# LokomotivATMega328RevA.net
KiCad netlist of a schematic drawn in EAGLE
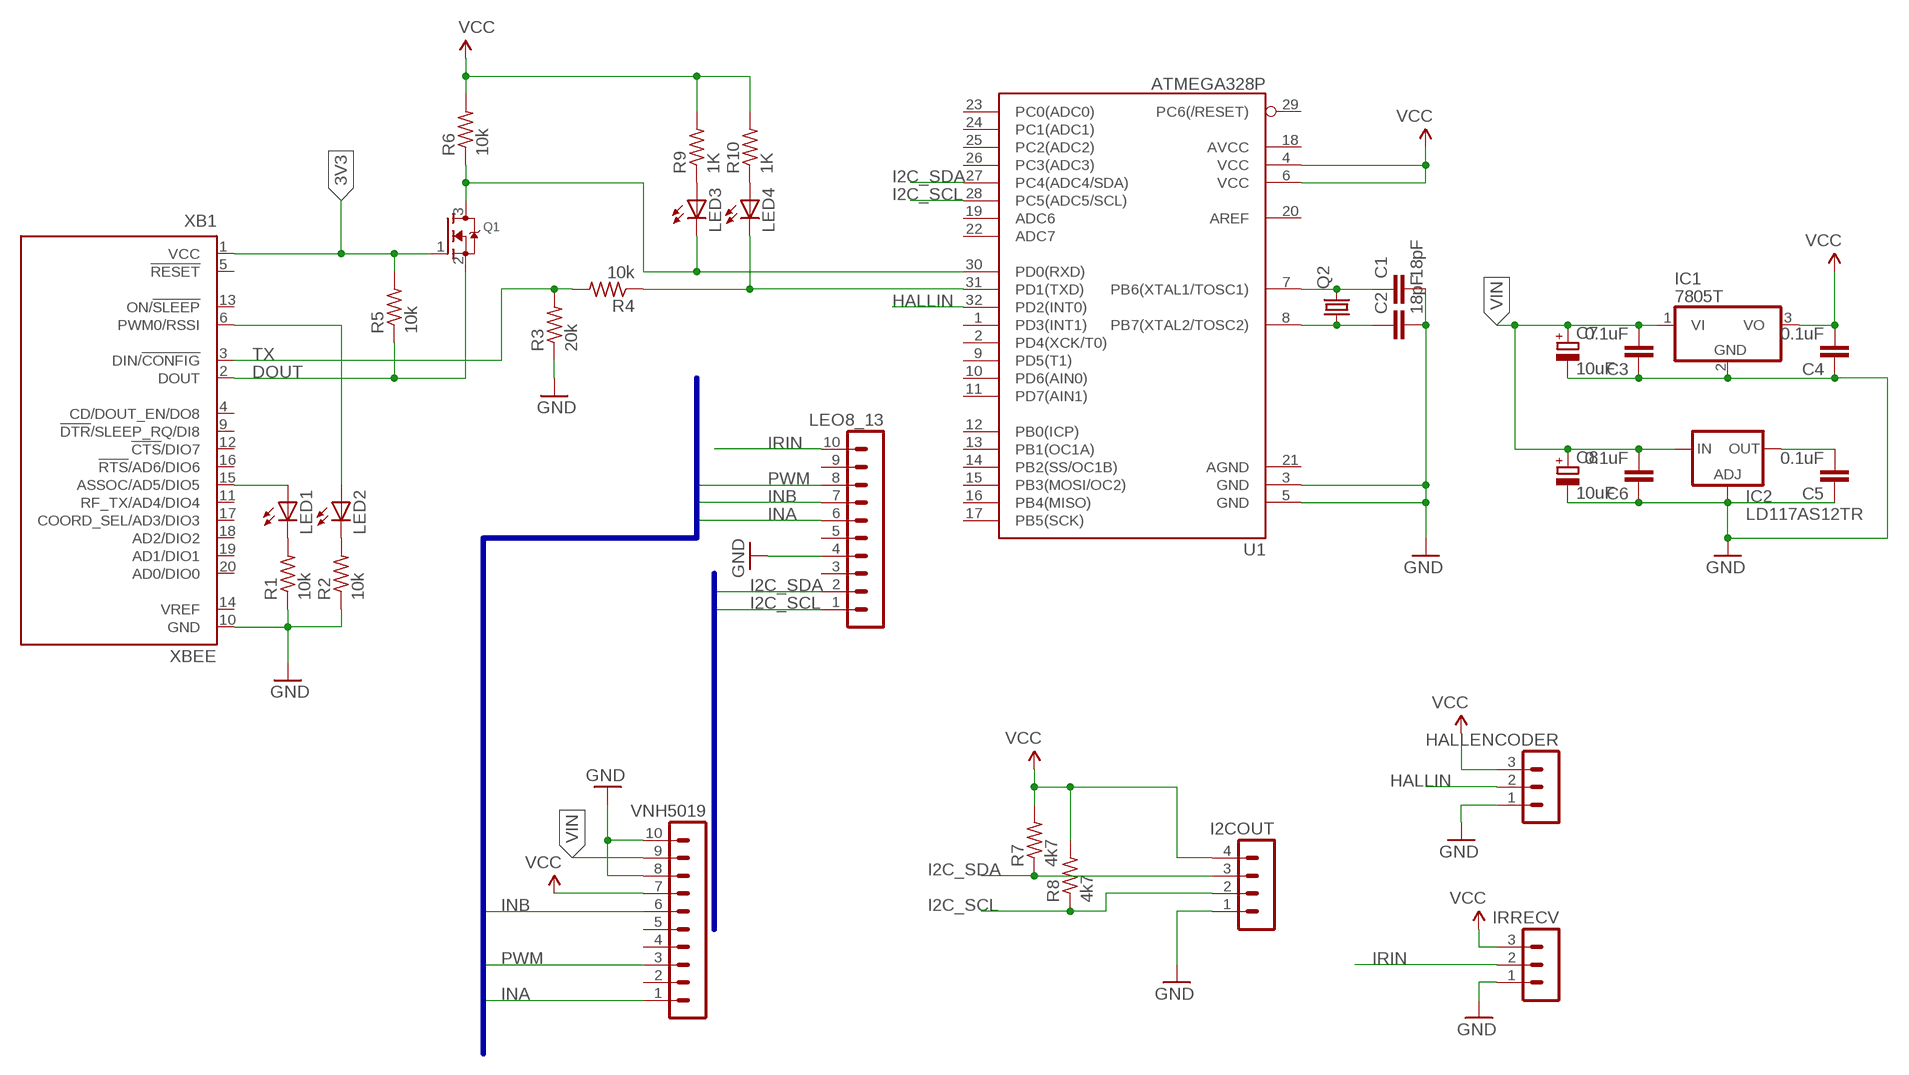
[diagram p0: schematic, sheet 1]

(export (version "E")
  (design (tool "Eeschema 10.0.6"))
  (components
    (comp (ref "C1")
      (value "18pF")
      (footprint "eagle-import:0603-CAP")
      (libsource (lib "eagle-import") (part "CAP0603-CAP"))
    )
    (comp (ref "C2")
      (value "18pF")
      (footprint "eagle-import:0603-CAP")
      (libsource (lib "eagle-import") (part "CAP0603-CAP"))
    )
    (comp (ref "C3")
      (value "0.1uF")
      (footprint "eagle-import:0603-CAP")
      (libsource (lib "eagle-import") (part "CAP0603-CAP"))
    )
    (comp (ref "C4")
      (value "0.1uF")
      (footprint "eagle-import:0603-CAP")
      (libsource (lib "eagle-import") (part "CAP0603-CAP"))
    )
    (comp (ref "C5")
      (value "0.1uF")
      (footprint "eagle-import:0603-CAP")
      (libsource (lib "eagle-import") (part "CAP0603-CAP"))
    )
    (comp (ref "C6")
      (value "0.1uF")
      (footprint "eagle-import:0603-CAP")
      (libsource (lib "eagle-import") (part "CAP0603-CAP"))
    )
    (comp (ref "C7")
      (value "10uF")
      (footprint "eagle-import:E3,5-10")
      (libsource (lib "eagle-import") (part "CPOL-EUE3.5-10"))
    )
    (comp (ref "C8")
      (value "10uF")
      (footprint "eagle-import:E3,5-10")
      (libsource (lib "eagle-import") (part "CPOL-EUE3.5-10"))
    )
    (comp (ref "HALLENCODER")
      (value "MA03-1")
      (footprint "eagle-import:MA03-1")
      (libsource (lib "eagle-import") (part "MA03-1"))
    )
    (comp (ref "I2COUT")
      (value "MA04-1")
      (footprint "eagle-import:MA04-1")
      (libsource (lib "eagle-import") (part "MA04-1"))
    )
    (comp (ref "IC1")
      (value "7805T")
      (footprint "eagle-import:TO220H")
      (libsource (lib "eagle-import") (part "78T05"))
    )
    (comp (ref "IC2")
      (value "LD117AS12TR")
      (footprint "eagle-import:SOT223")
      (libsource (lib "eagle-import") (part "LD117A?S12TR"))
    )
    (comp (ref "IRRECV")
      (value "MA03-1")
      (footprint "eagle-import:MA03-1")
      (libsource (lib "eagle-import") (part "MA03-1"))
    )
    (comp (ref "LED1")
      (value "LED-FKIT-1206")
      (footprint "eagle-import:FKIT-LED-1206")
      (libsource (lib "eagle-import") (part "LED-FKIT-1206"))
    )
    (comp (ref "LED2")
      (value "LED-FKIT-1206")
      (footprint "eagle-import:FKIT-LED-1206")
      (libsource (lib "eagle-import") (part "LED-FKIT-1206"))
    )
    (comp (ref "LED3")
      (value "LED-FKIT-1206")
      (footprint "eagle-import:FKIT-LED-1206")
      (libsource (lib "eagle-import") (part "LED-FKIT-1206"))
    )
    (comp (ref "LED4")
      (value "LED-FKIT-1206")
      (footprint "eagle-import:FKIT-LED-1206")
      (libsource (lib "eagle-import") (part "LED-FKIT-1206"))
    )
    (comp (ref "LEO8_13")
      (value "MA10-1")
      (footprint "eagle-import:MA10-1")
      (libsource (lib "eagle-import") (part "MA10-1"))
    )
    (comp (ref "Q1")
      (value "MOSFET-NREFLOW")
      (footprint "eagle-import:SOT23")
      (libsource (lib "eagle-import") (part "MOSFET-NREFLOW"))
    )
    (comp (ref "Q2")
      (value "CRYSTALSM49")
      (footprint "eagle-import:SM49")
      (libsource (lib "eagle-import") (part "CRYSTALSM49"))
    )
    (comp (ref "R1")
      (value "10k")
      (footprint "eagle-import:R0805")
      (libsource (lib "eagle-import") (part "R-US_R0805"))
    )
    (comp (ref "R2")
      (value "10k")
      (footprint "eagle-import:R0805")
      (libsource (lib "eagle-import") (part "R-US_R0805"))
    )
    (comp (ref "R3")
      (value "20k")
      (footprint "eagle-import:R0805")
      (libsource (lib "eagle-import") (part "R-US_R0805"))
    )
    (comp (ref "R4")
      (value "10k")
      (footprint "eagle-import:R0805")
      (libsource (lib "eagle-import") (part "R-US_R0805"))
    )
    (comp (ref "R5")
      (value "10k")
      (footprint "eagle-import:R0805")
      (libsource (lib "eagle-import") (part "R-US_R0805"))
    )
    (comp (ref "R6")
      (value "10k")
      (footprint "eagle-import:R0805")
      (libsource (lib "eagle-import") (part "R-US_R0805"))
    )
    (comp (ref "R7")
      (value "4k7")
      (footprint "eagle-import:R0805")
      (libsource (lib "eagle-import") (part "R-US_R0805"))
    )
    (comp (ref "R8")
      (value "4k7")
      (footprint "eagle-import:R0805")
      (libsource (lib "eagle-import") (part "R-US_R0805"))
    )
    (comp (ref "R9")
      (value "1K")
      (footprint "eagle-import:R0805")
      (libsource (lib "eagle-import") (part "R-US_R0805"))
    )
    (comp (ref "R10")
      (value "1K")
      (footprint "eagle-import:R0805")
      (libsource (lib "eagle-import") (part "R-US_R0805"))
    )
    (comp (ref "U1")
      (value "ATMEGA328P")
      (footprint "eagle-import:TQFP32-08")
      (libsource (lib "eagle-import") (part "ATMEGA328_SMT"))
    )
    (comp (ref "VNH5019")
      (value "MA10-1")
      (footprint "eagle-import:MA10-1")
      (libsource (lib "eagle-import") (part "MA10-1"))
    )
    (comp (ref "XB1")
      (value "XBEE")
      (footprint "eagle-import:XBEE")
      (fields (field (name "MPN") "XBP24-Z7UIT-004"))
      (libsource (lib "eagle-import") (part "XBEE"))
    )
  )
  (nets
    (net (code "1") (name "/DOUT") (class "Default")
      (node (ref "Q1") (pin "2") (pinfunction "S_2") (pintype "bidirectional"))
      (node (ref "R5") (pin "1") (pinfunction "1_1") (pintype "passive"))
      (node (ref "XB1") (pin "2") (pinfunction "DOUT_2") (pintype "output"))
    )
    (net (code "2") (name "/HALLIN") (class "Default")
      (node (ref "HALLENCODER") (pin "2") (pinfunction "2_2") (pintype "passive"))
      (node (ref "U1") (pin "32") (pinfunction "PD2(INT0)_32") (pintype "bidirectional"))
    )
    (net (code "3") (name "/I2C_SCL") (class "Default")
      (node (ref "I2COUT") (pin "2") (pinfunction "2_2") (pintype "passive"))
      (node (ref "LEO8_13") (pin "1") (pinfunction "1_1") (pintype "passive"))
      (node (ref "R8") (pin "1") (pinfunction "1_1") (pintype "passive"))
      (node (ref "U1") (pin "28") (pinfunction "PC5(ADC5/SCL)_28") (pintype "bidirectional"))
    )
    (net (code "4") (name "/I2C_SDA") (class "Default")
      (node (ref "I2COUT") (pin "3") (pinfunction "3_3") (pintype "passive"))
      (node (ref "LEO8_13") (pin "2") (pinfunction "2_2") (pintype "passive"))
      (node (ref "R7") (pin "1") (pinfunction "1_1") (pintype "passive"))
      (node (ref "U1") (pin "27") (pinfunction "PC4(ADC4/SDA)_27") (pintype "bidirectional"))
    )
    (net (code "5") (name "/INA") (class "Default")
      (node (ref "LEO8_13") (pin "6") (pinfunction "6_6") (pintype "passive"))
      (node (ref "VNH5019") (pin "1") (pinfunction "1_1") (pintype "passive"))
    )
    (net (code "6") (name "/INB") (class "Default")
      (node (ref "LEO8_13") (pin "7") (pinfunction "7_7") (pintype "passive"))
      (node (ref "VNH5019") (pin "6") (pinfunction "6_6") (pintype "passive"))
    )
    (net (code "7") (name "/IRIN") (class "Default")
      (node (ref "IRRECV") (pin "2") (pinfunction "2_2") (pintype "passive"))
      (node (ref "LEO8_13") (pin "10") (pinfunction "10_10") (pintype "passive"))
    )
    (net (code "8") (name "/PWM") (class "Default")
      (node (ref "LEO8_13") (pin "8") (pinfunction "8_8") (pintype "passive"))
      (node (ref "VNH5019") (pin "3") (pinfunction "3_3") (pintype "passive"))
    )
    (net (code "9") (name "/TX") (class "Default")
      (node (ref "R3") (pin "2") (pinfunction "2_2") (pintype "passive"))
      (node (ref "R4") (pin "2") (pinfunction "2_2") (pintype "passive"))
      (node (ref "XB1") (pin "3") (pinfunction "DIN/~{CONFIG}_3") (pintype "input"))
    )
    (net (code "10") (name "3V3") (class "Default")
      (node (ref "Q1") (pin "1") (pinfunction "G_1") (pintype "bidirectional"))
      (node (ref "R5") (pin "2") (pinfunction "2_2") (pintype "passive"))
      (node (ref "XB1") (pin "1") (pinfunction "VCC_1") (pintype "power_in"))
    )
    (net (code "11") (name "GND") (class "Default")
      (node (ref "C1") (pin "2") (pinfunction "2_2") (pintype "passive"))
      (node (ref "C2") (pin "2") (pinfunction "2_2") (pintype "passive"))
      (node (ref "C3") (pin "1") (pinfunction "1_1") (pintype "passive"))
      (node (ref "C4") (pin "1") (pinfunction "1_1") (pintype "passive"))
      (node (ref "C5") (pin "1") (pinfunction "1_1") (pintype "passive"))
      (node (ref "C6") (pin "1") (pinfunction "1_1") (pintype "passive"))
      (node (ref "C7") (pin "-") (pinfunction "-_-") (pintype "passive"))
      (node (ref "C8") (pin "-") (pinfunction "-_-") (pintype "passive"))
      (node (ref "HALLENCODER") (pin "1") (pinfunction "1_1") (pintype "passive"))
      (node (ref "I2COUT") (pin "1") (pinfunction "1_1") (pintype "passive"))
      (node (ref "IC1") (pin "2") (pinfunction "GND_2") (pintype "passive"))
      (node (ref "IC2") (pin "1") (pinfunction "ADJ_1") (pintype "input"))
      (node (ref "IRRECV") (pin "1") (pinfunction "1_1") (pintype "passive"))
      (node (ref "LEO8_13") (pin "4") (pinfunction "4_4") (pintype "passive"))
      (node (ref "R1") (pin "1") (pinfunction "1_1") (pintype "passive"))
      (node (ref "R2") (pin "1") (pinfunction "1_1") (pintype "passive"))
      (node (ref "R3") (pin "1") (pinfunction "1_1") (pintype "passive"))
      (node (ref "U1") (pin "3") (pinfunction "GND_3") (pintype "bidirectional"))
      (node (ref "U1") (pin "5") (pinfunction "GND_5") (pintype "bidirectional"))
      (node (ref "VNH5019") (pin "10") (pinfunction "10_10") (pintype "passive"))
      (node (ref "VNH5019") (pin "8") (pinfunction "8_8") (pintype "passive"))
      (node (ref "XB1") (pin "10") (pinfunction "GND_10") (pintype "power_in"))
    )
    (net (code "12") (name "Net-(IC2-OUT)") (class "Default")
      (node (ref "C5") (pin "2") (pinfunction "2_2") (pintype "passive"))
      (node (ref "IC2") (pin "4") (pinfunction "OUT_4") (pintype "passive"))
    )
    (net (code "13") (name "Net-(LED1-PadC)") (class "Default")
      (node (ref "LED1") (pin "C") (pinfunction "C_C") (pintype "passive"))
      (node (ref "R1") (pin "2") (pinfunction "2_2") (pintype "passive"))
    )
    (net (code "14") (name "Net-(LED2-PadC)") (class "Default")
      (node (ref "LED2") (pin "C") (pinfunction "C_C") (pintype "passive"))
      (node (ref "R2") (pin "2") (pinfunction "2_2") (pintype "passive"))
    )
    (net (code "15") (name "Net-(LED3-PadA)") (class "Default")
      (node (ref "LED3") (pin "A") (pinfunction "A_A") (pintype "passive"))
      (node (ref "R9") (pin "1") (pinfunction "1_1") (pintype "passive"))
    )
    (net (code "16") (name "Net-(LED4-PadA)") (class "Default")
      (node (ref "LED4") (pin "A") (pinfunction "A_A") (pintype "passive"))
      (node (ref "R10") (pin "1") (pinfunction "1_1") (pintype "passive"))
    )
    (net (code "17") (name "Net-(Q1-D)") (class "Default")
      (node (ref "LED3") (pin "C") (pinfunction "C_C") (pintype "passive"))
      (node (ref "Q1") (pin "3") (pinfunction "D_3") (pintype "bidirectional"))
      (node (ref "R6") (pin "1") (pinfunction "1_1") (pintype "passive"))
      (node (ref "U1") (pin "30") (pinfunction "PD0(RXD)_30") (pintype "bidirectional"))
    )
    (net (code "18") (name "Net-(U1-PB6(XTAL1{slash}TOSC1))") (class "Default")
      (node (ref "C1") (pin "1") (pinfunction "1_1") (pintype "passive"))
      (node (ref "Q2") (pin "2") (pinfunction "2_2") (pintype "passive"))
      (node (ref "U1") (pin "7") (pinfunction "PB6(XTAL1/TOSC1)_7") (pintype "bidirectional"))
    )
    (net (code "19") (name "Net-(U1-PB7(XTAL2{slash}TOSC2))") (class "Default")
      (node (ref "C2") (pin "1") (pinfunction "1_1") (pintype "passive"))
      (node (ref "Q2") (pin "1") (pinfunction "1_1") (pintype "passive"))
      (node (ref "U1") (pin "8") (pinfunction "PB7(XTAL2/TOSC2)_8") (pintype "bidirectional"))
    )
    (net (code "20") (name "Net-(U1-PD1(TXD))") (class "Default")
      (node (ref "LED4") (pin "C") (pinfunction "C_C") (pintype "passive"))
      (node (ref "R4") (pin "1") (pinfunction "1_1") (pintype "passive"))
      (node (ref "U1") (pin "31") (pinfunction "PD1(TXD)_31") (pintype "bidirectional"))
    )
    (net (code "21") (name "Net-(XB1-ASSOC{slash}AD5{slash}DIO5)") (class "Default")
      (node (ref "LED1") (pin "A") (pinfunction "A_A") (pintype "passive"))
      (node (ref "XB1") (pin "15") (pinfunction "ASSOC/AD5/DIO5_15") (pintype "bidirectional"))
    )
    (net (code "22") (name "Net-(XB1-PWM0{slash}RSSI)") (class "Default")
      (node (ref "LED2") (pin "A") (pinfunction "A_A") (pintype "passive"))
      (node (ref "XB1") (pin "6") (pinfunction "PWM0/RSSI_6") (pintype "output"))
    )
    (net (code "23") (name "VCC") (class "Default")
      (node (ref "C4") (pin "2") (pinfunction "2_2") (pintype "passive"))
      (node (ref "HALLENCODER") (pin "3") (pinfunction "3_3") (pintype "passive"))
      (node (ref "I2COUT") (pin "4") (pinfunction "4_4") (pintype "passive"))
      (node (ref "IC1") (pin "3") (pinfunction "VO_3") (pintype "passive"))
      (node (ref "IRRECV") (pin "3") (pinfunction "3_3") (pintype "passive"))
      (node (ref "R10") (pin "2") (pinfunction "2_2") (pintype "passive"))
      (node (ref "R6") (pin "2") (pinfunction "2_2") (pintype "passive"))
      (node (ref "R7") (pin "2") (pinfunction "2_2") (pintype "passive"))
      (node (ref "R8") (pin "2") (pinfunction "2_2") (pintype "passive"))
      (node (ref "R9") (pin "2") (pinfunction "2_2") (pintype "passive"))
      (node (ref "U1") (pin "4") (pinfunction "VCC_4") (pintype "bidirectional"))
      (node (ref "U1") (pin "6") (pinfunction "VCC_6") (pintype "bidirectional"))
      (node (ref "VNH5019") (pin "7") (pinfunction "7_7") (pintype "passive"))
    )
    (net (code "24") (name "VIN") (class "Default")
      (node (ref "C3") (pin "2") (pinfunction "2_2") (pintype "passive"))
      (node (ref "C6") (pin "2") (pinfunction "2_2") (pintype "passive"))
      (node (ref "C7") (pin "+") (pinfunction "+_+") (pintype "passive"))
      (node (ref "C8") (pin "+") (pinfunction "+_+") (pintype "passive"))
      (node (ref "IC1") (pin "1") (pinfunction "VI_1") (pintype "input"))
      (node (ref "IC2") (pin "3") (pinfunction "IN_3") (pintype "input"))
      (node (ref "VNH5019") (pin "9") (pinfunction "9_9") (pintype "passive"))
    )
    (net (code "25") (name "unconnected-(LEO8_13-Pad3)") (class "Default")
      (node (ref "LEO8_13") (pin "3") (pinfunction "3_3") (pintype "passive"))
    )
    (net (code "26") (name "unconnected-(LEO8_13-Pad5)") (class "Default")
      (node (ref "LEO8_13") (pin "5") (pinfunction "5_5") (pintype "passive"))
    )
    (net (code "27") (name "unconnected-(LEO8_13-Pad9)") (class "Default")
      (node (ref "LEO8_13") (pin "9") (pinfunction "9_9") (pintype "passive"))
    )
    (net (code "28") (name "unconnected-(U1-ADC6-Pad19)") (class "Default")
      (node (ref "U1") (pin "19") (pinfunction "ADC6_19") (pintype "bidirectional"))
    )
    (net (code "29") (name "unconnected-(U1-ADC7-Pad22)") (class "Default")
      (node (ref "U1") (pin "22") (pinfunction "ADC7_22") (pintype "bidirectional"))
    )
    (net (code "30") (name "unconnected-(U1-AGND-Pad21)") (class "Default")
      (node (ref "U1") (pin "21") (pinfunction "AGND_21") (pintype "bidirectional"))
    )
    (net (code "31") (name "unconnected-(U1-AREF-Pad20)") (class "Default")
      (node (ref "U1") (pin "20") (pinfunction "AREF_20") (pintype "bidirectional"))
    )
    (net (code "32") (name "unconnected-(U1-AVCC-Pad18)") (class "Default")
      (node (ref "U1") (pin "18") (pinfunction "AVCC_18") (pintype "bidirectional"))
    )
    (net (code "33") (name "unconnected-(U1-PB0(ICP)-Pad12)") (class "Default")
      (node (ref "U1") (pin "12") (pinfunction "PB0(ICP)_12") (pintype "bidirectional"))
    )
    (net (code "34") (name "unconnected-(U1-PB1(OC1A)-Pad13)") (class "Default")
      (node (ref "U1") (pin "13") (pinfunction "PB1(OC1A)_13") (pintype "bidirectional"))
    )
    (net (code "35") (name "unconnected-(U1-PB2(SS{slash}OC1B)-Pad14)") (class "Default")
      (node (ref "U1") (pin "14") (pinfunction "PB2(SS/OC1B)_14") (pintype "bidirectional"))
    )
    (net (code "36") (name "unconnected-(U1-PB3(MOSI{slash}OC2)-Pad15)") (class "Default")
      (node (ref "U1") (pin "15") (pinfunction "PB3(MOSI/OC2)_15") (pintype "bidirectional"))
    )
    (net (code "37") (name "unconnected-(U1-PB4(MISO)-Pad16)") (class "Default")
      (node (ref "U1") (pin "16") (pinfunction "PB4(MISO)_16") (pintype "bidirectional"))
    )
    (net (code "38") (name "unconnected-(U1-PB5(SCK)-Pad17)") (class "Default")
      (node (ref "U1") (pin "17") (pinfunction "PB5(SCK)_17") (pintype "bidirectional"))
    )
    (net (code "39") (name "unconnected-(U1-PC0(ADC0)-Pad23)") (class "Default")
      (node (ref "U1") (pin "23") (pinfunction "PC0(ADC0)_23") (pintype "bidirectional"))
    )
    (net (code "40") (name "unconnected-(U1-PC1(ADC1)-Pad24)") (class "Default")
      (node (ref "U1") (pin "24") (pinfunction "PC1(ADC1)_24") (pintype "bidirectional"))
    )
    (net (code "41") (name "unconnected-(U1-PC2(ADC2)-Pad25)") (class "Default")
      (node (ref "U1") (pin "25") (pinfunction "PC2(ADC2)_25") (pintype "bidirectional"))
    )
    (net (code "42") (name "unconnected-(U1-PC3(ADC3)-Pad26)") (class "Default")
      (node (ref "U1") (pin "26") (pinfunction "PC3(ADC3)_26") (pintype "bidirectional"))
    )
    (net (code "43") (name "unconnected-(U1-PC6({slash}RESET)-Pad29)") (class "Default")
      (node (ref "U1") (pin "29") (pinfunction "PC6(/RESET)_29") (pintype "bidirectional"))
    )
    (net (code "44") (name "unconnected-(U1-PD3(INT1)-Pad1)") (class "Default")
      (node (ref "U1") (pin "1") (pinfunction "PD3(INT1)_1") (pintype "bidirectional"))
    )
    (net (code "45") (name "unconnected-(U1-PD4(XCK{slash}T0)-Pad2)") (class "Default")
      (node (ref "U1") (pin "2") (pinfunction "PD4(XCK/T0)_2") (pintype "bidirectional"))
    )
    (net (code "46") (name "unconnected-(U1-PD5(T1)-Pad9)") (class "Default")
      (node (ref "U1") (pin "9") (pinfunction "PD5(T1)_9") (pintype "bidirectional"))
    )
    (net (code "47") (name "unconnected-(U1-PD6(AIN0)-Pad10)") (class "Default")
      (node (ref "U1") (pin "10") (pinfunction "PD6(AIN0)_10") (pintype "bidirectional"))
    )
    (net (code "48") (name "unconnected-(U1-PD7(AIN1)-Pad11)") (class "Default")
      (node (ref "U1") (pin "11") (pinfunction "PD7(AIN1)_11") (pintype "bidirectional"))
    )
    (net (code "49") (name "unconnected-(VNH5019-Pad2)") (class "Default")
      (node (ref "VNH5019") (pin "2") (pinfunction "2_2") (pintype "passive"))
    )
    (net (code "50") (name "unconnected-(VNH5019-Pad4)") (class "Default")
      (node (ref "VNH5019") (pin "4") (pinfunction "4_4") (pintype "passive"))
    )
    (net (code "51") (name "unconnected-(VNH5019-Pad5)") (class "Default")
      (node (ref "VNH5019") (pin "5") (pinfunction "5_5") (pintype "passive"))
    )
    (net (code "52") (name "unconnected-(XB1-AD0{slash}DIO0-Pad20)") (class "Default")
      (node (ref "XB1") (pin "20") (pinfunction "AD0/DIO0_20") (pintype "bidirectional"))
    )
    (net (code "53") (name "unconnected-(XB1-AD1{slash}DIO1-Pad19)") (class "Default")
      (node (ref "XB1") (pin "19") (pinfunction "AD1/DIO1_19") (pintype "bidirectional"))
    )
    (net (code "54") (name "unconnected-(XB1-AD2{slash}DIO2-Pad18)") (class "Default")
      (node (ref "XB1") (pin "18") (pinfunction "AD2/DIO2_18") (pintype "bidirectional"))
    )
    (net (code "55") (name "unconnected-(XB1-CD{slash}DOUT_EN{slash}DO8-Pad4)") (class "Default")
      (node (ref "XB1") (pin "4") (pinfunction "CD/DOUT_EN/DO8_4") (pintype "output"))
    )
    (net (code "56") (name "unconnected-(XB1-COORD_SEL{slash}AD3{slash}DIO3-Pad17)") (class "Default")
      (node (ref "XB1") (pin "17") (pinfunction "COORD_SEL/AD3/DIO3_17") (pintype "bidirectional"))
    )
    (net (code "57") (name "unconnected-(XB1-ON{slash}~{SLEEP}-Pad13)") (class "Default")
      (node (ref "XB1") (pin "13") (pinfunction "ON/~{SLEEP}_13") (pintype "output"))
    )
    (net (code "58") (name "unconnected-(XB1-RF_TX{slash}AD4{slash}DIO4-Pad11)") (class "Default")
      (node (ref "XB1") (pin "11") (pinfunction "RF_TX/AD4/DIO4_11") (pintype "bidirectional"))
    )
    (net (code "59") (name "unconnected-(XB1-VREF-Pad14)") (class "Default")
      (node (ref "XB1") (pin "14") (pinfunction "VREF_14") (pintype "input"))
    )
    (net (code "60") (name "unconnected-(XB1-~{CTS}{slash}DIO7-Pad12)") (class "Default")
      (node (ref "XB1") (pin "12") (pinfunction "~{CTS}/DIO7_12") (pintype "bidirectional"))
    )
    (net (code "61") (name "unconnected-(XB1-~{DTR}{slash}SLEEP_RQ{slash}DI8-Pad9)") (class "Default")
      (node (ref "XB1") (pin "9") (pinfunction "~{DTR}/SLEEP_RQ/DI8_9") (pintype "bidirectional"))
    )
    (net (code "62") (name "unconnected-(XB1-~{RESET}-Pad5)") (class "Default")
      (node (ref "XB1") (pin "5") (pinfunction "~{RESET}_5") (pintype "input"))
    )
    (net (code "63") (name "unconnected-(XB1-~{RTS}{slash}AD6{slash}DIO6-Pad16)") (class "Default")
      (node (ref "XB1") (pin "16") (pinfunction "~{RTS}/AD6/DIO6_16") (pintype "bidirectional"))
    )
  )
)
